# trans_vi_char.net
KiCad netlist of a schematic drawn in EAGLE
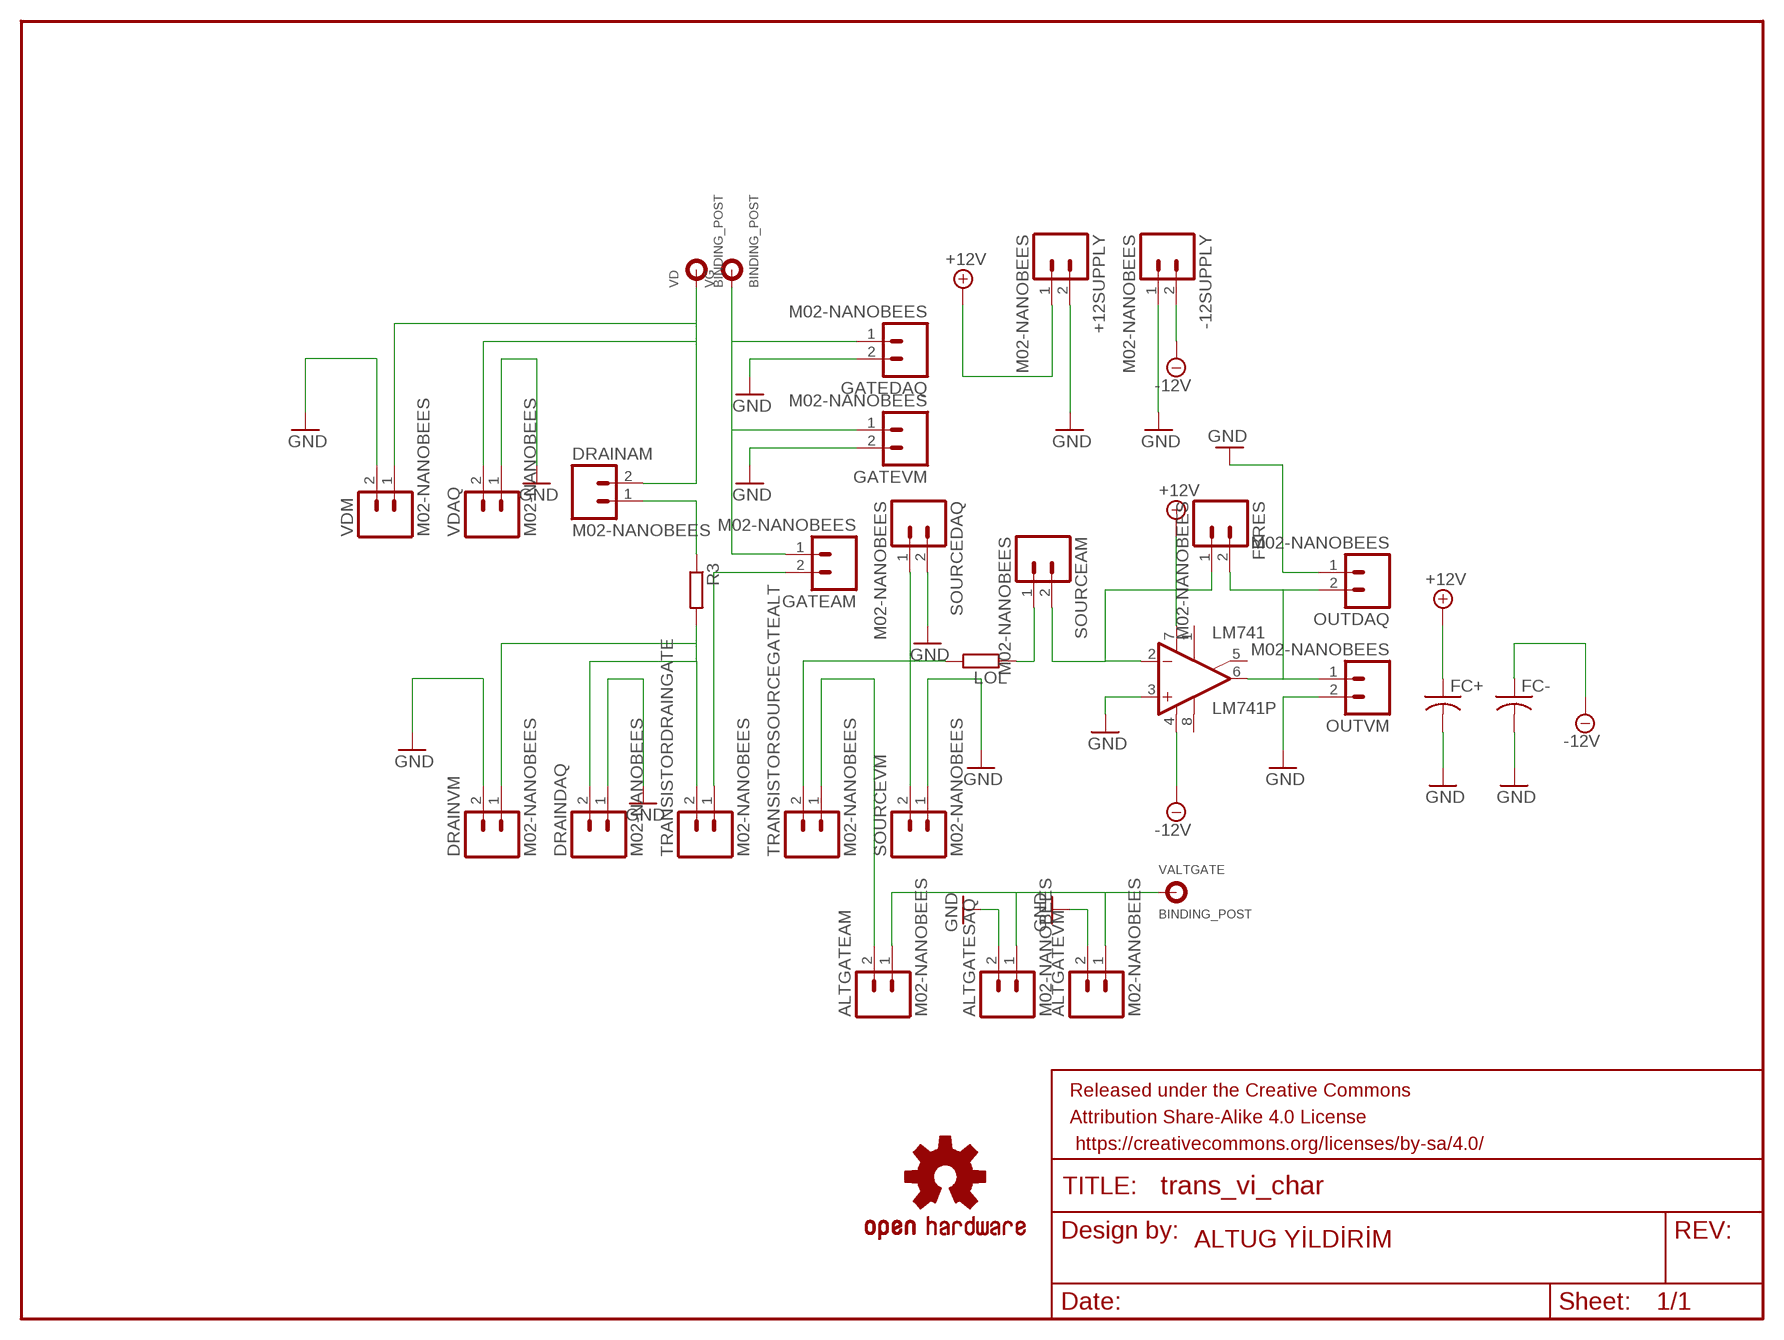
[diagram p0: schematic, sheet 1]

(export (version "E")
  (design (tool "Eeschema 10.0.6"))
  (components
    (comp (ref "+12SUPPLY")
      (value "M02-NANOBEES")
      (footprint "eagle-import:M02-NANOBEES")
      (libsource (lib "eagle-import") (part "M02-NANOBEES"))
    )
    (comp (ref "-12SUPPLY")
      (value "M02-NANOBEES")
      (footprint "eagle-import:M02-NANOBEES")
      (libsource (lib "eagle-import") (part "M02-NANOBEES"))
    )
    (comp (ref "ALTGATEAM")
      (value "M02-NANOBEES")
      (footprint "eagle-import:M02-NANOBEES")
      (libsource (lib "eagle-import") (part "M02-NANOBEES"))
    )
    (comp (ref "ALTGATESAQ")
      (value "M02-NANOBEES")
      (footprint "eagle-import:M02-NANOBEES")
      (libsource (lib "eagle-import") (part "M02-NANOBEES"))
    )
    (comp (ref "ALTGATEVM")
      (value "M02-NANOBEES")
      (footprint "eagle-import:M02-NANOBEES")
      (libsource (lib "eagle-import") (part "M02-NANOBEES"))
    )
    (comp (ref "DRAINAM")
      (value "M02-NANOBEES")
      (footprint "eagle-import:M02-NANOBEES")
      (libsource (lib "eagle-import") (part "M02-NANOBEES"))
    )
    (comp (ref "DRAINDAQ")
      (value "M02-NANOBEES")
      (footprint "eagle-import:M02-NANOBEES")
      (libsource (lib "eagle-import") (part "M02-NANOBEES"))
    )
    (comp (ref "DRAINVM")
      (value "M02-NANOBEES")
      (footprint "eagle-import:M02-NANOBEES")
      (libsource (lib "eagle-import") (part "M02-NANOBEES"))
    )
    (comp (ref "FBRES")
      (value "M02-NANOBEES")
      (footprint "eagle-import:M02-NANOBEES")
      (libsource (lib "eagle-import") (part "M02-NANOBEES"))
    )
    (comp (ref "FC+")
      (value "C-US025-025X050")
      (footprint "eagle-import:C025-025X050")
      (libsource (lib "eagle-import") (part "C-US025-025X050"))
    )
    (comp (ref "FC-")
      (value "C-US025-025X050")
      (footprint "eagle-import:C025-025X050")
      (libsource (lib "eagle-import") (part "C-US025-025X050"))
    )
    (comp (ref "FRAME1")
      (value "FRAME-LETTER")
      (footprint "eagle-import:CREATIVE_COMMONS")
      (libsource (lib "eagle-import") (part "FRAME-LETTER"))
    )
    (comp (ref "GATEAM")
      (value "M02-NANOBEES")
      (footprint "eagle-import:M02-NANOBEES")
      (libsource (lib "eagle-import") (part "M02-NANOBEES"))
    )
    (comp (ref "GATEDAQ")
      (value "M02-NANOBEES")
      (footprint "eagle-import:M02-NANOBEES")
      (libsource (lib "eagle-import") (part "M02-NANOBEES"))
    )
    (comp (ref "GATEVM")
      (value "M02-NANOBEES")
      (footprint "eagle-import:M02-NANOBEES")
      (libsource (lib "eagle-import") (part "M02-NANOBEES"))
    )
    (comp (ref "LM741")
      (value "LM741P")
      (footprint "eagle-import:DIL08")
      (libsource (lib "eagle-import") (part "741PLM"))
    )
    (comp (ref "LOGO1")
      (value "OSHW-LOGOM")
      (footprint "eagle-import:OSHW-LOGO-M")
      (libsource (lib "eagle-import") (part "OSHW-LOGOM"))
    )
    (comp (ref "LOL")
      (value "R-EU_0204/7")
      (footprint "eagle-import:0204_7")
      (libsource (lib "eagle-import") (part "R-EU_0204/7"))
    )
    (comp (ref "OUTDAQ")
      (value "M02-NANOBEES")
      (footprint "eagle-import:M02-NANOBEES")
      (libsource (lib "eagle-import") (part "M02-NANOBEES"))
    )
    (comp (ref "OUTVM")
      (value "M02-NANOBEES")
      (footprint "eagle-import:M02-NANOBEES")
      (libsource (lib "eagle-import") (part "M02-NANOBEES"))
    )
    (comp (ref "R3")
      (value "R-EU_0204/7")
      (footprint "eagle-import:0204_7")
      (libsource (lib "eagle-import") (part "R-EU_0204/7"))
    )
    (comp (ref "SOURCEAM")
      (value "M02-NANOBEES")
      (footprint "eagle-import:M02-NANOBEES")
      (libsource (lib "eagle-import") (part "M02-NANOBEES"))
    )
    (comp (ref "SOURCEDAQ")
      (value "M02-NANOBEES")
      (footprint "eagle-import:M02-NANOBEES")
      (libsource (lib "eagle-import") (part "M02-NANOBEES"))
    )
    (comp (ref "SOURCEVM")
      (value "M02-NANOBEES")
      (footprint "eagle-import:M02-NANOBEES")
      (libsource (lib "eagle-import") (part "M02-NANOBEES"))
    )
    (comp (ref "TRANSISTORDRAINGATE")
      (value "M02-NANOBEES")
      (footprint "eagle-import:M02-NANOBEES")
      (libsource (lib "eagle-import") (part "M02-NANOBEES"))
    )
    (comp (ref "TRANSISTORSOURCEGATEALT")
      (value "M02-NANOBEES")
      (footprint "eagle-import:M02-NANOBEES")
      (libsource (lib "eagle-import") (part "M02-NANOBEES"))
    )
    (comp (ref "VALTGATE")
      (value "BINDING_POST")
      (footprint "eagle-import:BINDING_POST")
      (libsource (lib "eagle-import") (part "BINDING_POST"))
    )
    (comp (ref "VD")
      (value "BINDING_POST")
      (footprint "eagle-import:BINDING_POST")
      (libsource (lib "eagle-import") (part "BINDING_POST"))
    )
    (comp (ref "VDAQ")
      (value "M02-NANOBEES")
      (footprint "eagle-import:M02-NANOBEES")
      (libsource (lib "eagle-import") (part "M02-NANOBEES"))
    )
    (comp (ref "VDM")
      (value "M02-NANOBEES")
      (footprint "eagle-import:M02-NANOBEES")
      (libsource (lib "eagle-import") (part "M02-NANOBEES"))
    )
    (comp (ref "VG")
      (value "BINDING_POST")
      (footprint "eagle-import:BINDING_POST")
      (libsource (lib "eagle-import") (part "BINDING_POST"))
    )
  )
  (nets
    (net (code "1") (name "+12V") (class "Default")
      (node (ref "+12SUPPLY") (pin "1") (pinfunction "1_1") (pintype "passive"))
      (node (ref "FC+") (pin "1") (pinfunction "1_1") (pintype "passive"))
      (node (ref "LM741") (pin "7") (pinfunction "V+_7") (pintype "power_in"))
    )
    (net (code "2") (name "-12V") (class "Default")
      (node (ref "-12SUPPLY") (pin "2") (pinfunction "2_2") (pintype "passive"))
      (node (ref "FC-") (pin "1") (pinfunction "1_1") (pintype "passive"))
      (node (ref "LM741") (pin "4") (pinfunction "V-_4") (pintype "power_in"))
    )
    (net (code "3") (name "GND") (class "Default")
      (node (ref "+12SUPPLY") (pin "2") (pinfunction "2_2") (pintype "passive"))
      (node (ref "-12SUPPLY") (pin "1") (pinfunction "1_1") (pintype "passive"))
      (node (ref "ALTGATESAQ") (pin "2") (pinfunction "2_2") (pintype "passive"))
      (node (ref "ALTGATEVM") (pin "2") (pinfunction "2_2") (pintype "passive"))
      (node (ref "DRAINDAQ") (pin "1") (pinfunction "1_1") (pintype "passive"))
      (node (ref "DRAINVM") (pin "2") (pinfunction "2_2") (pintype "passive"))
      (node (ref "FC+") (pin "2") (pinfunction "2_2") (pintype "passive"))
      (node (ref "FC-") (pin "2") (pinfunction "2_2") (pintype "passive"))
      (node (ref "GATEDAQ") (pin "2") (pinfunction "2_2") (pintype "passive"))
      (node (ref "GATEVM") (pin "2") (pinfunction "2_2") (pintype "passive"))
      (node (ref "LM741") (pin "3") (pinfunction "-IN_3") (pintype "input"))
      (node (ref "OUTDAQ") (pin "1") (pinfunction "1_1") (pintype "passive"))
      (node (ref "OUTVM") (pin "2") (pinfunction "2_2") (pintype "passive"))
      (node (ref "SOURCEDAQ") (pin "2") (pinfunction "2_2") (pintype "passive"))
      (node (ref "SOURCEVM") (pin "1") (pinfunction "1_1") (pintype "passive"))
      (node (ref "VDAQ") (pin "1") (pinfunction "1_1") (pintype "passive"))
      (node (ref "VDM") (pin "2") (pinfunction "2_2") (pintype "passive"))
    )
    (net (code "4") (name "Net-(ALTGATEAM-Pad1)") (class "Default")
      (node (ref "ALTGATEAM") (pin "1") (pinfunction "1_1") (pintype "passive"))
      (node (ref "ALTGATESAQ") (pin "1") (pinfunction "1_1") (pintype "passive"))
      (node (ref "ALTGATEVM") (pin "1") (pinfunction "1_1") (pintype "passive"))
      (node (ref "VALTGATE") (pin "P$1") (pinfunction "P$1_P$1") (pintype "bidirectional"))
    )
    (net (code "5") (name "Net-(ALTGATEAM-Pad2)") (class "Default")
      (node (ref "ALTGATEAM") (pin "2") (pinfunction "2_2") (pintype "passive"))
      (node (ref "TRANSISTORSOURCEGATEALT") (pin "1") (pinfunction "1_1") (pintype "passive"))
    )
    (net (code "6") (name "Net-(DRAINAM-Pad1)") (class "Default")
      (node (ref "DRAINAM") (pin "1") (pinfunction "1_1") (pintype "passive"))
      (node (ref "R3") (pin "1") (pinfunction "1_1") (pintype "passive"))
    )
    (net (code "7") (name "Net-(DRAINAM-Pad2)") (class "Default")
      (node (ref "DRAINAM") (pin "2") (pinfunction "2_2") (pintype "passive"))
      (node (ref "VD") (pin "P$1") (pinfunction "P$1_P$1") (pintype "bidirectional"))
      (node (ref "VDAQ") (pin "2") (pinfunction "2_2") (pintype "passive"))
      (node (ref "VDM") (pin "1") (pinfunction "1_1") (pintype "passive"))
    )
    (net (code "8") (name "Net-(DRAINDAQ-Pad2)") (class "Default")
      (node (ref "DRAINDAQ") (pin "2") (pinfunction "2_2") (pintype "passive"))
      (node (ref "DRAINVM") (pin "1") (pinfunction "1_1") (pintype "passive"))
      (node (ref "R3") (pin "2") (pinfunction "2_2") (pintype "passive"))
      (node (ref "TRANSISTORDRAINGATE") (pin "2") (pinfunction "2_2") (pintype "passive"))
    )
    (net (code "9") (name "Net-(GATEAM-Pad1)") (class "Default")
      (node (ref "GATEAM") (pin "1") (pinfunction "1_1") (pintype "passive"))
      (node (ref "GATEDAQ") (pin "1") (pinfunction "1_1") (pintype "passive"))
      (node (ref "GATEVM") (pin "1") (pinfunction "1_1") (pintype "passive"))
      (node (ref "VG") (pin "P$1") (pinfunction "P$1_P$1") (pintype "bidirectional"))
    )
    (net (code "10") (name "Net-(GATEAM-Pad2)") (class "Default")
      (node (ref "GATEAM") (pin "2") (pinfunction "2_2") (pintype "passive"))
      (node (ref "TRANSISTORDRAINGATE") (pin "1") (pinfunction "1_1") (pintype "passive"))
    )
    (net (code "11") (name "Net-(LM741-+IN)") (class "Default")
      (node (ref "FBRES") (pin "1") (pinfunction "1_1") (pintype "passive"))
      (node (ref "LM741") (pin "2") (pinfunction "+IN_2") (pintype "input"))
      (node (ref "SOURCEAM") (pin "2") (pinfunction "2_2") (pintype "passive"))
    )
    (net (code "12") (name "Net-(LM741-OUT)") (class "Default")
      (node (ref "FBRES") (pin "2") (pinfunction "2_2") (pintype "passive"))
      (node (ref "LM741") (pin "6") (pinfunction "OUT_6") (pintype "output"))
      (node (ref "OUTDAQ") (pin "2") (pinfunction "2_2") (pintype "passive"))
      (node (ref "OUTVM") (pin "1") (pinfunction "1_1") (pintype "passive"))
    )
    (net (code "13") (name "Net-(LOL-Pad1)") (class "Default")
      (node (ref "LOL") (pin "1") (pinfunction "1_1") (pintype "passive"))
      (node (ref "SOURCEAM") (pin "1") (pinfunction "1_1") (pintype "passive"))
    )
    (net (code "14") (name "Net-(LOL-Pad2)") (class "Default")
      (node (ref "LOL") (pin "2") (pinfunction "2_2") (pintype "passive"))
      (node (ref "SOURCEDAQ") (pin "1") (pinfunction "1_1") (pintype "passive"))
      (node (ref "SOURCEVM") (pin "2") (pinfunction "2_2") (pintype "passive"))
      (node (ref "TRANSISTORSOURCEGATEALT") (pin "2") (pinfunction "2_2") (pintype "passive"))
    )
    (net (code "15") (name "unconnected-(LM741-ON1-Pad1)") (class "Default")
      (node (ref "LM741") (pin "1") (pinfunction "ON1_1") (pintype "passive"))
    )
    (net (code "16") (name "unconnected-(LM741-ON2-Pad5)") (class "Default")
      (node (ref "LM741") (pin "5") (pinfunction "ON2_5") (pintype "passive"))
    )
    (net (code "17") (name "unconnected-(LM741-OPT-Pad8)") (class "Default")
      (node (ref "LM741") (pin "8") (pinfunction "OPT_8") (pintype "passive"))
    )
  )
)
